# 15_EXP_IO.net
KiCad netlist of a schematic drawn in Altium Designer
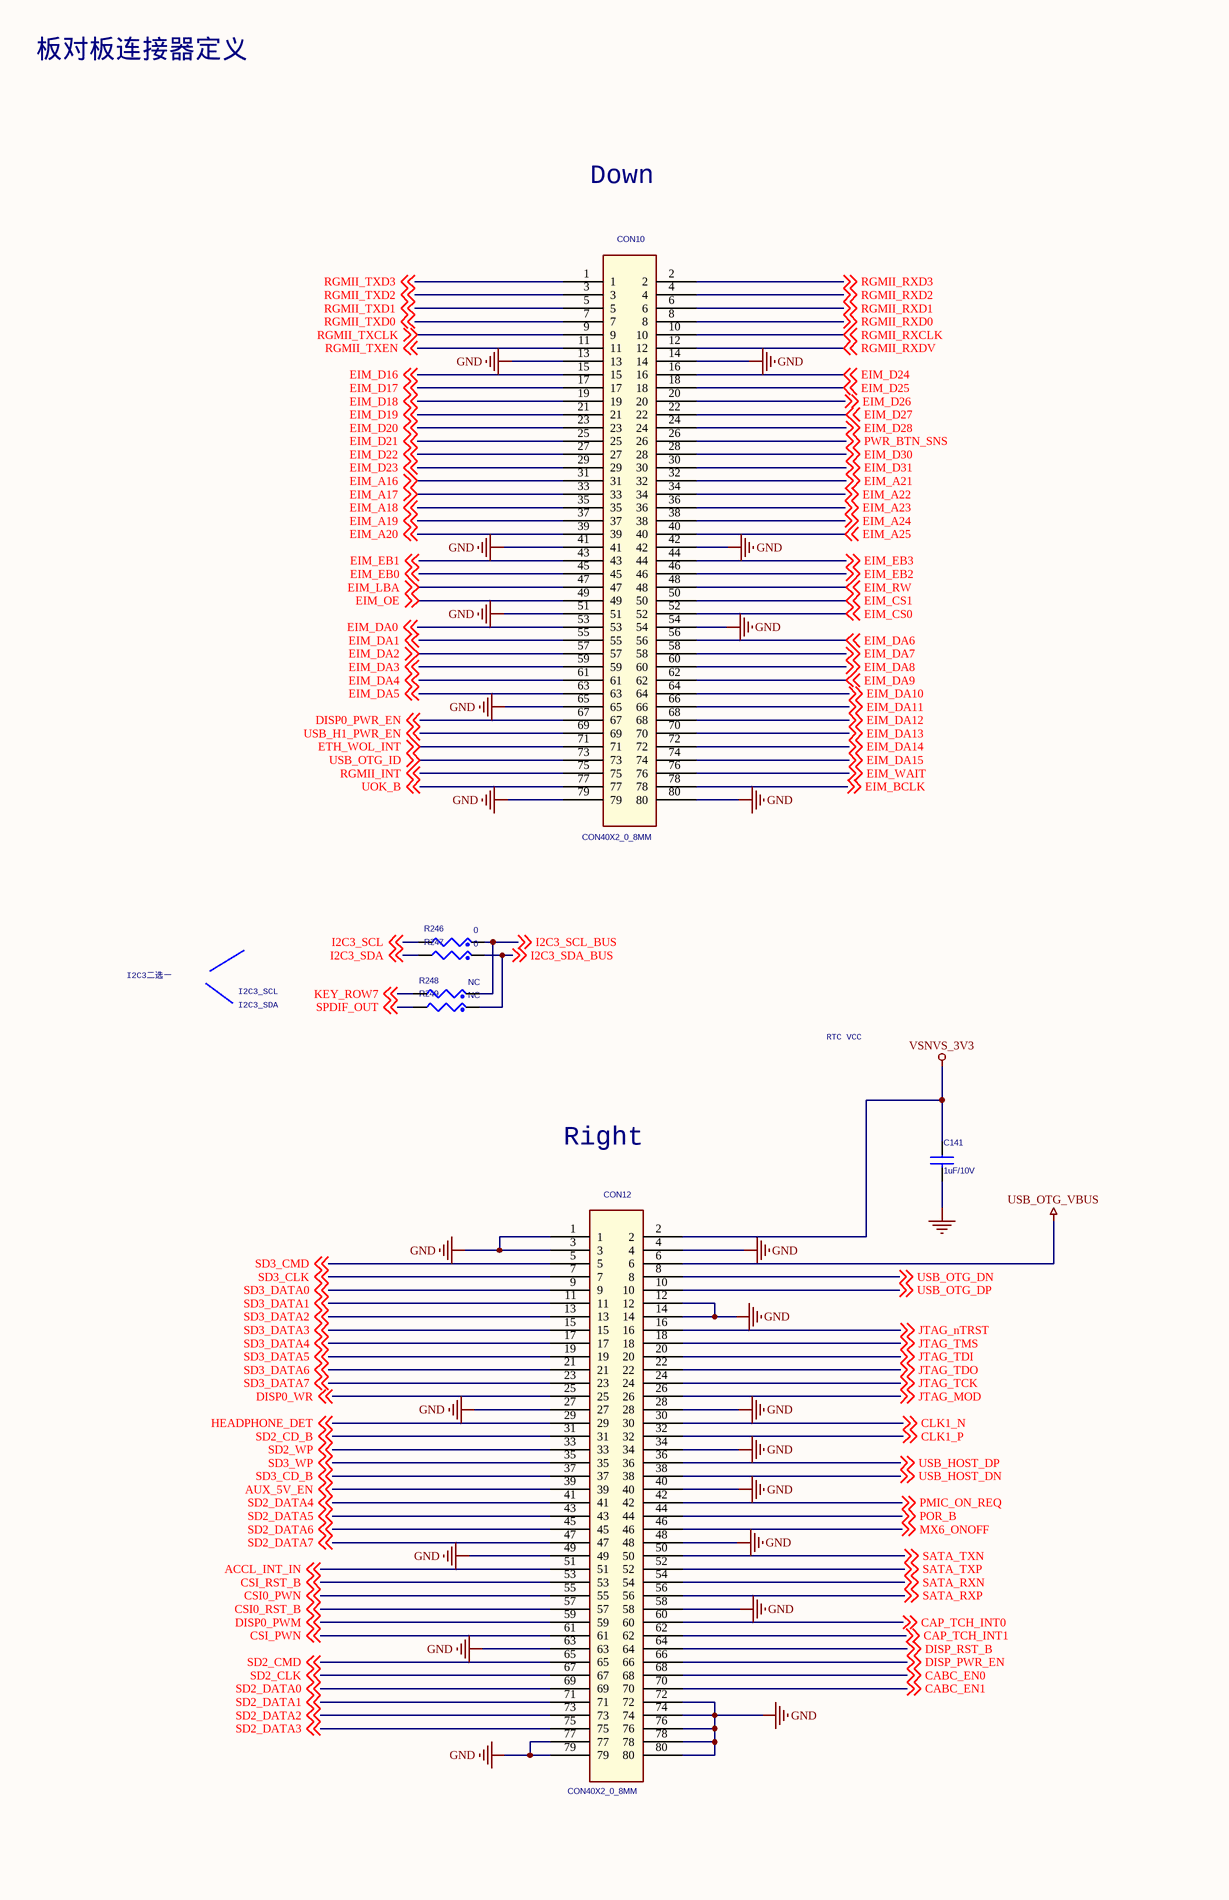
[diagram p0: 15 EXP_IO.SchDoc, left]
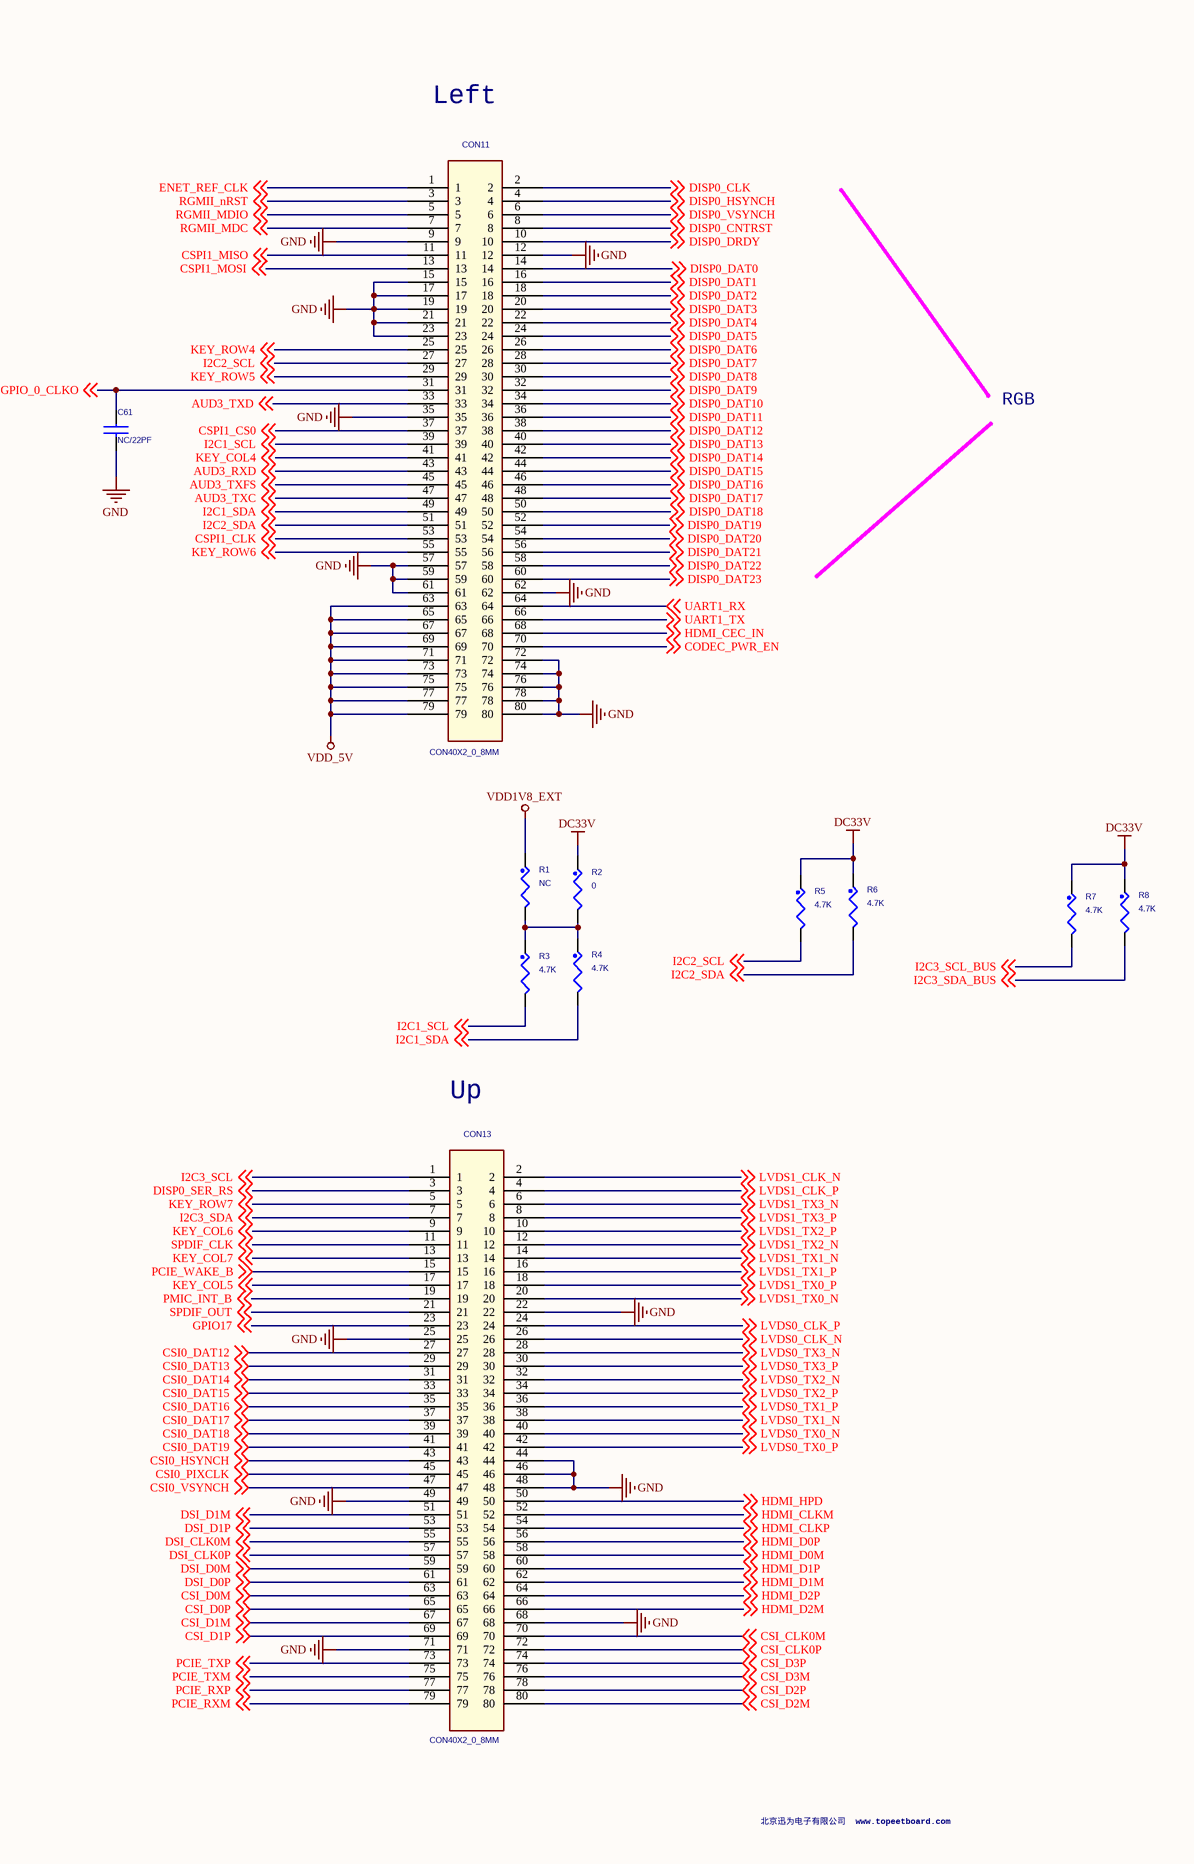
[diagram p1: 15 EXP_IO.SchDoc, right]

(export (version "E")
  (design (tool "Eeschema 10.0.6"))
  (components
    (comp (ref "C61") (value "NC/22PF") (footprint "C0603") (libsource (lib "*") (part "C0603_0_Dup1")))
    (comp (ref "C141") (value "1uF/10V") (footprint "C0603") (libsource (lib "*") (part "C0603_0_Dup1")))
    (comp (ref "CON10")
      (value "CON40X2_0_8MM")
      (footprint "CON40X2_0_8MM")
      (libsource (lib "*") (part "CON40X2_0_8MM"))
    )
    (comp (ref "CON11")
      (value "CON40X2_0_8MM")
      (footprint "CON40X2_0_8MM")
      (libsource (lib "*") (part "CON40X2_0_8MM"))
    )
    (comp (ref "CON12")
      (value "CON40X2_0_8MM")
      (footprint "CON40X2_0_8MM")
      (libsource (lib "*") (part "CON40X2_0_8MM"))
    )
    (comp (ref "CON13")
      (value "CON40X2_0_8MM")
      (footprint "CON40X2_0_8MM")
      (libsource (lib "*") (part "CON40X2_0_8MM"))
    )
    (comp (ref "R1")
      (value "NC")
      (description "RES MF ZERO OHM 1/10W -- 0402")
      (libsource (lib "*") (part "RES_Dup1"))
    )
    (comp (ref "R2")
      (value "0")
      (description "RES MF ZERO OHM 1/10W -- 0402")
      (libsource (lib "*") (part "RES_Dup1"))
    )
    (comp (ref "R3")
      (value "4.7K")
      (description "RES MF ZERO OHM 1/10W -- 0402")
      (libsource (lib "*") (part "RES_Dup1"))
    )
    (comp (ref "R4")
      (value "4.7K")
      (description "RES MF ZERO OHM 1/10W -- 0402")
      (libsource (lib "*") (part "RES_Dup1"))
    )
    (comp (ref "R5")
      (value "4.7K")
      (description "RES MF ZERO OHM 1/10W -- 0402")
      (libsource (lib "*") (part "RES_Dup1"))
    )
    (comp (ref "R6")
      (value "4.7K")
      (description "RES MF ZERO OHM 1/10W -- 0402")
      (libsource (lib "*") (part "RES_Dup1"))
    )
    (comp (ref "R7")
      (value "4.7K")
      (description "RES MF ZERO OHM 1/10W -- 0402")
      (libsource (lib "*") (part "RES_Dup1"))
    )
    (comp (ref "R8")
      (value "4.7K")
      (description "RES MF ZERO OHM 1/10W -- 0402")
      (libsource (lib "*") (part "RES_Dup1"))
    )
    (comp (ref "R246")
      (value "0")
      (description "RES MF 33 OHM 1/16W 5% 0402")
      (fields (field (name "TOLERANCE") "5%"))
      (libsource (lib "*") (part "RES_Dup1"))
    )
    (comp (ref "R247")
      (value "0")
      (description "RES MF 33 OHM 1/16W 5% 0402")
      (fields (field (name "TOLERANCE") "5%"))
      (libsource (lib "*") (part "RES_Dup1"))
    )
    (comp (ref "R248")
      (value "NC")
      (description "RES MF 33 OHM 1/16W 5% 0402")
      (fields (field (name "TOLERANCE") "5%"))
      (libsource (lib "*") (part "RES_Dup1"))
    )
    (comp (ref "R249")
      (value "NC")
      (description "RES MF 33 OHM 1/16W 5% 0402")
      (fields (field (name "TOLERANCE") "5%"))
      (libsource (lib "*") (part "RES_Dup1"))
    )
  )
  (nets
    (net (code "1") (name "ACCL_INT_IN") (class "Default")
      (node (ref "CON12") (pin "51") (pinfunction "51_51") (pintype "passive"))
    )
    (net (code "2") (name "AUD3_RXD") (class "Default")
      (node (ref "CON11") (pin "43") (pinfunction "43_43") (pintype "passive"))
    )
    (net (code "3") (name "AUD3_TXC") (class "Default")
      (node (ref "CON11") (pin "47") (pinfunction "47_47") (pintype "passive"))
    )
    (net (code "4") (name "AUD3_TXD") (class "Default")
      (node (ref "CON11") (pin "33") (pinfunction "33_33") (pintype "passive"))
    )
    (net (code "5") (name "AUD3_TXFS") (class "Default")
      (node (ref "CON11") (pin "45") (pinfunction "45_45") (pintype "passive"))
    )
    (net (code "6") (name "AUX_5V_EN") (class "Default")
      (node (ref "CON12") (pin "39") (pinfunction "39_39") (pintype "passive"))
    )
    (net (code "7") (name "CABC_EN0") (class "Default")
      (node (ref "CON12") (pin "68") (pinfunction "68_68") (pintype "passive"))
    )
    (net (code "8") (name "CABC_EN1") (class "Default")
      (node (ref "CON12") (pin "70") (pinfunction "70_70") (pintype "passive"))
    )
    (net (code "9") (name "CAP_TCH_INT0") (class "Default")
      (node (ref "CON12") (pin "60") (pinfunction "60_60") (pintype "passive"))
    )
    (net (code "10") (name "CAP_TCH_INT1") (class "Default")
      (node (ref "CON12") (pin "62") (pinfunction "62_62") (pintype "passive"))
    )
    (net (code "11") (name "CLK1_N") (class "Default")
      (node (ref "CON12") (pin "30") (pinfunction "30_30") (pintype "passive"))
    )
    (net (code "12") (name "CLK1_P") (class "Default")
      (node (ref "CON12") (pin "32") (pinfunction "32_32") (pintype "passive"))
    )
    (net (code "13") (name "CODEC_PWR_EN") (class "Default")
      (node (ref "CON11") (pin "70") (pinfunction "70_70") (pintype "passive"))
    )
    (net (code "14") (name "CSI0_DAT12") (class "Default")
      (node (ref "CON13") (pin "27") (pinfunction "27_27") (pintype "passive"))
    )
    (net (code "15") (name "CSI0_DAT13") (class "Default")
      (node (ref "CON13") (pin "29") (pinfunction "29_29") (pintype "passive"))
    )
    (net (code "16") (name "CSI0_DAT14") (class "Default")
      (node (ref "CON13") (pin "31") (pinfunction "31_31") (pintype "passive"))
    )
    (net (code "17") (name "CSI0_DAT15") (class "Default")
      (node (ref "CON13") (pin "33") (pinfunction "33_33") (pintype "passive"))
    )
    (net (code "18") (name "CSI0_DAT16") (class "Default")
      (node (ref "CON13") (pin "35") (pinfunction "35_35") (pintype "passive"))
    )
    (net (code "19") (name "CSI0_DAT17") (class "Default")
      (node (ref "CON13") (pin "37") (pinfunction "37_37") (pintype "passive"))
    )
    (net (code "20") (name "CSI0_DAT18") (class "Default")
      (node (ref "CON13") (pin "39") (pinfunction "39_39") (pintype "passive"))
    )
    (net (code "21") (name "CSI0_DAT19") (class "Default")
      (node (ref "CON13") (pin "41") (pinfunction "41_41") (pintype "passive"))
    )
    (net (code "22") (name "CSI0_HSYNCH") (class "Default")
      (node (ref "CON13") (pin "43") (pinfunction "43_43") (pintype "passive"))
    )
    (net (code "23") (name "CSI0_PIXCLK") (class "Default")
      (node (ref "CON13") (pin "45") (pinfunction "45_45") (pintype "passive"))
    )
    (net (code "24") (name "CSI0_PWN") (class "Default")
      (node (ref "CON12") (pin "55") (pinfunction "55_55") (pintype "passive"))
    )
    (net (code "25") (name "CSI0_RST_B") (class "Default")
      (node (ref "CON12") (pin "57") (pinfunction "57_57") (pintype "passive"))
    )
    (net (code "26") (name "CSI0_VSYNCH") (class "Default")
      (node (ref "CON13") (pin "47") (pinfunction "47_47") (pintype "passive"))
    )
    (net (code "27") (name "CSI_CLK0M") (class "Default")
      (node (ref "CON13") (pin "70") (pinfunction "70_70") (pintype "passive"))
    )
    (net (code "28") (name "CSI_CLK0P") (class "Default")
      (node (ref "CON13") (pin "72") (pinfunction "72_72") (pintype "passive"))
    )
    (net (code "29") (name "CSI_D0M") (class "Default")
      (node (ref "CON13") (pin "63") (pinfunction "63_63") (pintype "passive"))
    )
    (net (code "30") (name "CSI_D0P") (class "Default")
      (node (ref "CON13") (pin "65") (pinfunction "65_65") (pintype "passive"))
    )
    (net (code "31") (name "CSI_D1M") (class "Default")
      (node (ref "CON13") (pin "67") (pinfunction "67_67") (pintype "passive"))
    )
    (net (code "32") (name "CSI_D1P") (class "Default")
      (node (ref "CON13") (pin "69") (pinfunction "69_69") (pintype "passive"))
    )
    (net (code "33") (name "CSI_D2M") (class "Default")
      (node (ref "CON13") (pin "80") (pinfunction "80_80") (pintype "passive"))
    )
    (net (code "34") (name "CSI_D2P") (class "Default")
      (node (ref "CON13") (pin "78") (pinfunction "78_78") (pintype "passive"))
    )
    (net (code "35") (name "CSI_D3M") (class "Default")
      (node (ref "CON13") (pin "76") (pinfunction "76_76") (pintype "passive"))
    )
    (net (code "36") (name "CSI_D3P") (class "Default")
      (node (ref "CON13") (pin "74") (pinfunction "74_74") (pintype "passive"))
    )
    (net (code "37") (name "CSI_PWN") (class "Default")
      (node (ref "CON12") (pin "61") (pinfunction "61_61") (pintype "passive"))
    )
    (net (code "38") (name "CSI_RST_B") (class "Default")
      (node (ref "CON12") (pin "53") (pinfunction "53_53") (pintype "passive"))
    )
    (net (code "39") (name "CSPI1_CLK") (class "Default")
      (node (ref "CON11") (pin "53") (pinfunction "53_53") (pintype "passive"))
    )
    (net (code "40") (name "CSPI1_CS0") (class "Default")
      (node (ref "CON11") (pin "37") (pinfunction "37_37") (pintype "passive"))
    )
    (net (code "41") (name "CSPI1_MISO") (class "Default")
      (node (ref "CON11") (pin "11") (pinfunction "11_11") (pintype "passive"))
    )
    (net (code "42") (name "CSPI1_MOSI") (class "Default")
      (node (ref "CON11") (pin "13") (pinfunction "13_13") (pintype "passive"))
    )
    (net (code "43") (name "DC33V") (class "Default")
      (node (ref "R2") (pin "1") (pinfunction "1_1") (pintype "passive"))
      (node (ref "R5") (pin "1") (pinfunction "1_1") (pintype "passive"))
      (node (ref "R6") (pin "1") (pinfunction "1_1") (pintype "passive"))
      (node (ref "R7") (pin "1") (pinfunction "1_1") (pintype "passive"))
      (node (ref "R8") (pin "1") (pinfunction "1_1") (pintype "passive"))
    )
    (net (code "44") (name "DISP0_CLK") (class "Default")
      (node (ref "CON11") (pin "2") (pinfunction "2_2") (pintype "passive"))
    )
    (net (code "45") (name "DISP0_CNTRST") (class "Default")
      (node (ref "CON11") (pin "8") (pinfunction "8_8") (pintype "passive"))
    )
    (net (code "46") (name "DISP0_DAT0") (class "Default")
      (node (ref "CON11") (pin "14") (pinfunction "14_14") (pintype "passive"))
    )
    (net (code "47") (name "DISP0_DAT1") (class "Default")
      (node (ref "CON11") (pin "16") (pinfunction "16_16") (pintype "passive"))
    )
    (net (code "48") (name "DISP0_DAT2") (class "Default")
      (node (ref "CON11") (pin "18") (pinfunction "18_18") (pintype "passive"))
    )
    (net (code "49") (name "DISP0_DAT3") (class "Default")
      (node (ref "CON11") (pin "20") (pinfunction "20_20") (pintype "passive"))
    )
    (net (code "50") (name "DISP0_DAT4") (class "Default")
      (node (ref "CON11") (pin "22") (pinfunction "22_22") (pintype "passive"))
    )
    (net (code "51") (name "DISP0_DAT5") (class "Default")
      (node (ref "CON11") (pin "24") (pinfunction "24_24") (pintype "passive"))
    )
    (net (code "52") (name "DISP0_DAT6") (class "Default")
      (node (ref "CON11") (pin "26") (pinfunction "26_26") (pintype "passive"))
    )
    (net (code "53") (name "DISP0_DAT7") (class "Default")
      (node (ref "CON11") (pin "28") (pinfunction "28_28") (pintype "passive"))
    )
    (net (code "54") (name "DISP0_DAT8") (class "Default")
      (node (ref "CON11") (pin "30") (pinfunction "30_30") (pintype "passive"))
    )
    (net (code "55") (name "DISP0_DAT9") (class "Default")
      (node (ref "CON11") (pin "32") (pinfunction "32_32") (pintype "passive"))
    )
    (net (code "56") (name "DISP0_DAT10") (class "Default")
      (node (ref "CON11") (pin "34") (pinfunction "34_34") (pintype "passive"))
    )
    (net (code "57") (name "DISP0_DAT11") (class "Default")
      (node (ref "CON11") (pin "36") (pinfunction "36_36") (pintype "passive"))
    )
    (net (code "58") (name "DISP0_DAT12") (class "Default")
      (node (ref "CON11") (pin "38") (pinfunction "38_38") (pintype "passive"))
    )
    (net (code "59") (name "DISP0_DAT13") (class "Default")
      (node (ref "CON11") (pin "40") (pinfunction "40_40") (pintype "passive"))
    )
    (net (code "60") (name "DISP0_DAT14") (class "Default")
      (node (ref "CON11") (pin "42") (pinfunction "42_42") (pintype "passive"))
    )
    (net (code "61") (name "DISP0_DAT15") (class "Default")
      (node (ref "CON11") (pin "44") (pinfunction "44_44") (pintype "passive"))
    )
    (net (code "62") (name "DISP0_DAT16") (class "Default")
      (node (ref "CON11") (pin "46") (pinfunction "46_46") (pintype "passive"))
    )
    (net (code "63") (name "DISP0_DAT17") (class "Default")
      (node (ref "CON11") (pin "48") (pinfunction "48_48") (pintype "passive"))
    )
    (net (code "64") (name "DISP0_DAT18") (class "Default")
      (node (ref "CON11") (pin "50") (pinfunction "50_50") (pintype "passive"))
    )
    (net (code "65") (name "DISP0_DAT19") (class "Default")
      (node (ref "CON11") (pin "52") (pinfunction "52_52") (pintype "passive"))
    )
    (net (code "66") (name "DISP0_DAT20") (class "Default")
      (node (ref "CON11") (pin "54") (pinfunction "54_54") (pintype "passive"))
    )
    (net (code "67") (name "DISP0_DAT21") (class "Default")
      (node (ref "CON11") (pin "56") (pinfunction "56_56") (pintype "passive"))
    )
    (net (code "68") (name "DISP0_DAT22") (class "Default")
      (node (ref "CON11") (pin "58") (pinfunction "58_58") (pintype "passive"))
    )
    (net (code "69") (name "DISP0_DAT23") (class "Default")
      (node (ref "CON11") (pin "60") (pinfunction "60_60") (pintype "passive"))
    )
    (net (code "70") (name "DISP0_DRDY") (class "Default")
      (node (ref "CON11") (pin "10") (pinfunction "10_10") (pintype "passive"))
    )
    (net (code "71") (name "DISP0_HSYNCH") (class "Default")
      (node (ref "CON11") (pin "4") (pinfunction "4_4") (pintype "passive"))
    )
    (net (code "72") (name "DISP0_PWM") (class "Default")
      (node (ref "CON12") (pin "59") (pinfunction "59_59") (pintype "passive"))
    )
    (net (code "73") (name "DISP0_PWR_EN") (class "Default")
      (node (ref "CON10") (pin "67") (pinfunction "67_67") (pintype "passive"))
    )
    (net (code "74") (name "DISP0_SER_RS") (class "Default")
      (node (ref "CON13") (pin "3") (pinfunction "3_3") (pintype "passive"))
    )
    (net (code "75") (name "DISP0_VSYNCH") (class "Default")
      (node (ref "CON11") (pin "6") (pinfunction "6_6") (pintype "passive"))
    )
    (net (code "76") (name "DISP0_WR") (class "Default")
      (node (ref "CON12") (pin "25") (pinfunction "25_25") (pintype "passive"))
    )
    (net (code "77") (name "DISP_PWR_EN") (class "Default")
      (node (ref "CON12") (pin "66") (pinfunction "66_66") (pintype "passive"))
    )
    (net (code "78") (name "DISP_RST_B") (class "Default")
      (node (ref "CON12") (pin "64") (pinfunction "64_64") (pintype "passive"))
    )
    (net (code "79") (name "DSI_CLK0M") (class "Default")
      (node (ref "CON13") (pin "55") (pinfunction "55_55") (pintype "passive"))
    )
    (net (code "80") (name "DSI_CLK0P") (class "Default")
      (node (ref "CON13") (pin "57") (pinfunction "57_57") (pintype "passive"))
    )
    (net (code "81") (name "DSI_D0M") (class "Default")
      (node (ref "CON13") (pin "59") (pinfunction "59_59") (pintype "passive"))
    )
    (net (code "82") (name "DSI_D0P") (class "Default")
      (node (ref "CON13") (pin "61") (pinfunction "61_61") (pintype "passive"))
    )
    (net (code "83") (name "DSI_D1M") (class "Default")
      (node (ref "CON13") (pin "51") (pinfunction "51_51") (pintype "passive"))
    )
    (net (code "84") (name "DSI_D1P") (class "Default")
      (node (ref "CON13") (pin "53") (pinfunction "53_53") (pintype "passive"))
    )
    (net (code "85") (name "EIM_A16") (class "Default")
      (node (ref "CON10") (pin "31") (pinfunction "31_31") (pintype "passive"))
    )
    (net (code "86") (name "EIM_A17") (class "Default")
      (node (ref "CON10") (pin "33") (pinfunction "33_33") (pintype "passive"))
    )
    (net (code "87") (name "EIM_A18") (class "Default")
      (node (ref "CON10") (pin "35") (pinfunction "35_35") (pintype "passive"))
    )
    (net (code "88") (name "EIM_A19") (class "Default")
      (node (ref "CON10") (pin "37") (pinfunction "37_37") (pintype "passive"))
    )
    (net (code "89") (name "EIM_A20") (class "Default")
      (node (ref "CON10") (pin "39") (pinfunction "39_39") (pintype "passive"))
    )
    (net (code "90") (name "EIM_A21") (class "Default")
      (node (ref "CON10") (pin "32") (pinfunction "32_32") (pintype "passive"))
    )
    (net (code "91") (name "EIM_A22") (class "Default")
      (node (ref "CON10") (pin "34") (pinfunction "34_34") (pintype "passive"))
    )
    (net (code "92") (name "EIM_A23") (class "Default")
      (node (ref "CON10") (pin "36") (pinfunction "36_36") (pintype "passive"))
    )
    (net (code "93") (name "EIM_A24") (class "Default")
      (node (ref "CON10") (pin "38") (pinfunction "38_38") (pintype "passive"))
    )
    (net (code "94") (name "EIM_A25") (class "Default")
      (node (ref "CON10") (pin "40") (pinfunction "40_40") (pintype "passive"))
    )
    (net (code "95") (name "EIM_BCLK") (class "Default")
      (node (ref "CON10") (pin "78") (pinfunction "78_78") (pintype "passive"))
    )
    (net (code "96") (name "EIM_CS0") (class "Default")
      (node (ref "CON10") (pin "52") (pinfunction "52_52") (pintype "passive"))
    )
    (net (code "97") (name "EIM_CS1") (class "Default")
      (node (ref "CON10") (pin "50") (pinfunction "50_50") (pintype "passive"))
    )
    (net (code "98") (name "EIM_D16") (class "Default")
      (node (ref "CON10") (pin "15") (pinfunction "15_15") (pintype "passive"))
    )
    (net (code "99") (name "EIM_D17") (class "Default")
      (node (ref "CON10") (pin "17") (pinfunction "17_17") (pintype "passive"))
    )
    (net (code "100") (name "EIM_D18") (class "Default")
      (node (ref "CON10") (pin "19") (pinfunction "19_19") (pintype "passive"))
    )
    (net (code "101") (name "EIM_D19") (class "Default")
      (node (ref "CON10") (pin "21") (pinfunction "21_21") (pintype "passive"))
    )
    (net (code "102") (name "EIM_D20") (class "Default")
      (node (ref "CON10") (pin "23") (pinfunction "23_23") (pintype "passive"))
    )
    (net (code "103") (name "EIM_D21") (class "Default")
      (node (ref "CON10") (pin "25") (pinfunction "25_25") (pintype "passive"))
    )
    (net (code "104") (name "EIM_D22") (class "Default")
      (node (ref "CON10") (pin "27") (pinfunction "27_27") (pintype "passive"))
    )
    (net (code "105") (name "EIM_D23") (class "Default")
      (node (ref "CON10") (pin "29") (pinfunction "29_29") (pintype "passive"))
    )
    (net (code "106") (name "EIM_D24") (class "Default")
      (node (ref "CON10") (pin "16") (pinfunction "16_16") (pintype "passive"))
    )
    (net (code "107") (name "EIM_D25") (class "Default")
      (node (ref "CON10") (pin "18") (pinfunction "18_18") (pintype "passive"))
    )
    (net (code "108") (name "EIM_D26") (class "Default")
      (node (ref "CON10") (pin "20") (pinfunction "20_20") (pintype "passive"))
    )
    (net (code "109") (name "EIM_D27") (class "Default")
      (node (ref "CON10") (pin "22") (pinfunction "22_22") (pintype "passive"))
    )
    (net (code "110") (name "EIM_D28") (class "Default")
      (node (ref "CON10") (pin "24") (pinfunction "24_24") (pintype "passive"))
    )
    (net (code "111") (name "EIM_D30") (class "Default")
      (node (ref "CON10") (pin "28") (pinfunction "28_28") (pintype "passive"))
    )
    (net (code "112") (name "EIM_D31") (class "Default")
      (node (ref "CON10") (pin "30") (pinfunction "30_30") (pintype "passive"))
    )
    (net (code "113") (name "EIM_DA0") (class "Default")
      (node (ref "CON10") (pin "53") (pinfunction "53_53") (pintype "passive"))
    )
    (net (code "114") (name "EIM_DA1") (class "Default")
      (node (ref "CON10") (pin "55") (pinfunction "55_55") (pintype "passive"))
    )
    (net (code "115") (name "EIM_DA2") (class "Default")
      (node (ref "CON10") (pin "57") (pinfunction "57_57") (pintype "passive"))
    )
    (net (code "116") (name "EIM_DA3") (class "Default")
      (node (ref "CON10") (pin "59") (pinfunction "59_59") (pintype "passive"))
    )
    (net (code "117") (name "EIM_DA4") (class "Default")
      (node (ref "CON10") (pin "61") (pinfunction "61_61") (pintype "passive"))
    )
    (net (code "118") (name "EIM_DA5") (class "Default")
      (node (ref "CON10") (pin "63") (pinfunction "63_63") (pintype "passive"))
    )
    (net (code "119") (name "EIM_DA6") (class "Default")
      (node (ref "CON10") (pin "56") (pinfunction "56_56") (pintype "passive"))
    )
    (net (code "120") (name "EIM_DA7") (class "Default")
      (node (ref "CON10") (pin "58") (pinfunction "58_58") (pintype "passive"))
    )
    (net (code "121") (name "EIM_DA8") (class "Default")
      (node (ref "CON10") (pin "60") (pinfunction "60_60") (pintype "passive"))
    )
    (net (code "122") (name "EIM_DA9") (class "Default")
      (node (ref "CON10") (pin "62") (pinfunction "62_62") (pintype "passive"))
    )
    (net (code "123") (name "EIM_DA10") (class "Default")
      (node (ref "CON10") (pin "64") (pinfunction "64_64") (pintype "passive"))
    )
    (net (code "124") (name "EIM_DA11") (class "Default")
      (node (ref "CON10") (pin "66") (pinfunction "66_66") (pintype "passive"))
    )
    (net (code "125") (name "EIM_DA12") (class "Default")
      (node (ref "CON10") (pin "68") (pinfunction "68_68") (pintype "passive"))
    )
    (net (code "126") (name "EIM_DA13") (class "Default")
      (node (ref "CON10") (pin "70") (pinfunction "70_70") (pintype "passive"))
    )
    (net (code "127") (name "EIM_DA14") (class "Default")
      (node (ref "CON10") (pin "72") (pinfunction "72_72") (pintype "passive"))
    )
    (net (code "128") (name "EIM_DA15") (class "Default")
      (node (ref "CON10") (pin "74") (pinfunction "74_74") (pintype "passive"))
    )
    (net (code "129") (name "EIM_EB0") (class "Default")
      (node (ref "CON10") (pin "45") (pinfunction "45_45") (pintype "passive"))
    )
    (net (code "130") (name "EIM_EB1") (class "Default")
      (node (ref "CON10") (pin "43") (pinfunction "43_43") (pintype "passive"))
    )
    (net (code "131") (name "EIM_EB2") (class "Default")
      (node (ref "CON10") (pin "46") (pinfunction "46_46") (pintype "passive"))
    )
    (net (code "132") (name "EIM_EB3") (class "Default")
      (node (ref "CON10") (pin "44") (pinfunction "44_44") (pintype "passive"))
    )
    (net (code "133") (name "EIM_LBA") (class "Default")
      (node (ref "CON10") (pin "47") (pinfunction "47_47") (pintype "passive"))
    )
    (net (code "134") (name "EIM_OE") (class "Default")
      (node (ref "CON10") (pin "49") (pinfunction "49_49") (pintype "passive"))
    )
    (net (code "135") (name "EIM_RW") (class "Default")
      (node (ref "CON10") (pin "48") (pinfunction "48_48") (pintype "passive"))
    )
    (net (code "136") (name "EIM_WAIT") (class "Default")
      (node (ref "CON10") (pin "76") (pinfunction "76_76") (pintype "passive"))
    )
    (net (code "137") (name "ENET_REF_CLK") (class "Default")
      (node (ref "CON11") (pin "1") (pinfunction "1_1") (pintype "passive"))
    )
    (net (code "138") (name "ETH_WOL_INT") (class "Default")
      (node (ref "CON10") (pin "71") (pinfunction "71_71") (pintype "passive"))
    )
    (net (code "139") (name "GND") (class "Default")
      (node (ref "C141") (pin "2") (pinfunction "2_2") (pintype "passive"))
      (node (ref "C61") (pin "2") (pinfunction "2_2") (pintype "passive"))
      (node (ref "CON10") (pin "13") (pinfunction "13_13") (pintype "passive"))
      (node (ref "CON10") (pin "14") (pinfunction "14_14") (pintype "passive"))
      (node (ref "CON10") (pin "41") (pinfunction "41_41") (pintype "passive"))
      (node (ref "CON10") (pin "42") (pinfunction "42_42") (pintype "passive"))
      (node (ref "CON10") (pin "51") (pinfunction "51_51") (pintype "passive"))
      (node (ref "CON10") (pin "54") (pinfunction "54_54") (pintype "passive"))
      (node (ref "CON10") (pin "65") (pinfunction "65_65") (pintype "passive"))
      (node (ref "CON10") (pin "79") (pinfunction "79_79") (pintype "passive"))
      (node (ref "CON10") (pin "80") (pinfunction "80_80") (pintype "passive"))
      (node (ref "CON11") (pin "12") (pinfunction "12_12") (pintype "passive"))
      (node (ref "CON11") (pin "15") (pinfunction "15_15") (pintype "passive"))
      (node (ref "CON11") (pin "17") (pinfunction "17_17") (pintype "passive"))
      (node (ref "CON11") (pin "19") (pinfunction "19_19") (pintype "passive"))
      (node (ref "CON11") (pin "21") (pinfunction "21_21") (pintype "passive"))
      (node (ref "CON11") (pin "23") (pinfunction "23_23") (pintype "passive"))
      (node (ref "CON11") (pin "35") (pinfunction "35_35") (pintype "passive"))
      (node (ref "CON11") (pin "57") (pinfunction "57_57") (pintype "passive"))
      (node (ref "CON11") (pin "59") (pinfunction "59_59") (pintype "passive"))
      (node (ref "CON11") (pin "61") (pinfunction "61_61") (pintype "passive"))
      (node (ref "CON11") (pin "62") (pinfunction "62_62") (pintype "passive"))
      (node (ref "CON11") (pin "72") (pinfunction "72_72") (pintype "passive"))
      (node (ref "CON11") (pin "74") (pinfunction "74_74") (pintype "passive"))
      (node (ref "CON11") (pin "76") (pinfunction "76_76") (pintype "passive"))
      (node (ref "CON11") (pin "78") (pinfunction "78_78") (pintype "passive"))
      (node (ref "CON11") (pin "80") (pinfunction "80_80") (pintype "passive"))
      (node (ref "CON11") (pin "9") (pinfunction "9_9") (pintype "passive"))
      (node (ref "CON12") (pin "1") (pinfunction "1_1") (pintype "passive"))
      (node (ref "CON12") (pin "12") (pinfunction "12_12") (pintype "passive"))
      (node (ref "CON12") (pin "14") (pinfunction "14_14") (pintype "passive"))
      (node (ref "CON12") (pin "27") (pinfunction "27_27") (pintype "passive"))
      (node (ref "CON12") (pin "28") (pinfunction "28_28") (pintype "passive"))
      (node (ref "CON12") (pin "3") (pinfunction "3_3") (pintype "passive"))
      (node (ref "CON12") (pin "34") (pinfunction "34_34") (pintype "passive"))
      (node (ref "CON12") (pin "4") (pinfunction "4_4") (pintype "passive"))
      (node (ref "CON12") (pin "40") (pinfunction "40_40") (pintype "passive"))
      (node (ref "CON12") (pin "48") (pinfunction "48_48") (pintype "passive"))
      (node (ref "CON12") (pin "49") (pinfunction "49_49") (pintype "passive"))
      (node (ref "CON12") (pin "58") (pinfunction "58_58") (pintype "passive"))
      (node (ref "CON12") (pin "63") (pinfunction "63_63") (pintype "passive"))
      (node (ref "CON12") (pin "72") (pinfunction "72_72") (pintype "passive"))
      (node (ref "CON12") (pin "74") (pinfunction "74_74") (pintype "passive"))
      (node (ref "CON12") (pin "76") (pinfunction "76_76") (pintype "passive"))
      (node (ref "CON12") (pin "77") (pinfunction "77_77") (pintype "passive"))
      (node (ref "CON12") (pin "78") (pinfunction "78_78") (pintype "passive"))
      (node (ref "CON12") (pin "79") (pinfunction "79_79") (pintype "passive"))
      (node (ref "CON12") (pin "80") (pinfunction "80_80") (pintype "passive"))
      (node (ref "CON13") (pin "22") (pinfunction "22_22") (pintype "passive"))
      (node (ref "CON13") (pin "25") (pinfunction "25_25") (pintype "passive"))
      (node (ref "CON13") (pin "44") (pinfunction "44_44") (pintype "passive"))
      (node (ref "CON13") (pin "46") (pinfunction "46_46") (pintype "passive"))
      (node (ref "CON13") (pin "48") (pinfunction "48_48") (pintype "passive"))
      (node (ref "CON13") (pin "49") (pinfunction "49_49") (pintype "passive"))
      (node (ref "CON13") (pin "68") (pinfunction "68_68") (pintype "passive"))
      (node (ref "CON13") (pin "71") (pinfunction "71_71") (pintype "passive"))
    )
    (net (code "140") (name "GPIO17") (class "Default")
      (node (ref "CON13") (pin "23") (pinfunction "23_23") (pintype "passive"))
    )
    (net (code "141") (name "GPIO_0_CLKO") (class "Default")
      (node (ref "C61") (pin "1") (pinfunction "1_1") (pintype "passive"))
      (node (ref "CON11") (pin "31") (pinfunction "31_31") (pintype "passive"))
    )
    (net (code "142") (name "HDMI_CEC_IN") (class "Default")
      (node (ref "CON11") (pin "68") (pinfunction "68_68") (pintype "passive"))
    )
    (net (code "143") (name "HDMI_CLKM") (class "Default")
      (node (ref "CON13") (pin "52") (pinfunction "52_52") (pintype "passive"))
    )
    (net (code "144") (name "HDMI_CLKP") (class "Default")
      (node (ref "CON13") (pin "54") (pinfunction "54_54") (pintype "passive"))
    )
    (net (code "145") (name "HDMI_D0M") (class "Default")
      (node (ref "CON13") (pin "58") (pinfunction "58_58") (pintype "passive"))
    )
    (net (code "146") (name "HDMI_D0P") (class "Default")
      (node (ref "CON13") (pin "56") (pinfunction "56_56") (pintype "passive"))
    )
    (net (code "147") (name "HDMI_D1M") (class "Default")
      (node (ref "CON13") (pin "62") (pinfunction "62_62") (pintype "passive"))
    )
    (net (code "148") (name "HDMI_D1P") (class "Default")
      (node (ref "CON13") (pin "60") (pinfunction "60_60") (pintype "passive"))
    )
    (net (code "149") (name "HDMI_D2M") (class "Default")
      (node (ref "CON13") (pin "66") (pinfunction "66_66") (pintype "passive"))
    )
    (net (code "150") (name "HDMI_D2P") (class "Default")
      (node (ref "CON13") (pin "64") (pinfunction "64_64") (pintype "passive"))
    )
    (net (code "151") (name "HDMI_HPD") (class "Default")
      (node (ref "CON13") (pin "50") (pinfunction "50_50") (pintype "passive"))
    )
    (net (code "152") (name "HEADPHONE_DET") (class "Default")
      (node (ref "CON12") (pin "29") (pinfunction "29_29") (pintype "passive"))
    )
    (net (code "153") (name "I2C1_SCL") (class "Default")
      (node (ref "CON11") (pin "39") (pinfunction "39_39") (pintype "passive"))
      (node (ref "R3") (pin "2") (pinfunction "2_2") (pintype "passive"))
    )
    (net (code "154") (name "I2C1_SDA") (class "Default")
      (node (ref "CON11") (pin "49") (pinfunction "49_49") (pintype "passive"))
      (node (ref "R4") (pin "2") (pinfunction "2_2") (pintype "passive"))
    )
    (net (code "155") (name "I2C2_SCL") (class "Default")
      (node (ref "CON11") (pin "27") (pinfunction "27_27") (pintype "passive"))
      (node (ref "R5") (pin "2") (pinfunction "2_2") (pintype "passive"))
    )
    (net (code "156") (name "I2C2_SDA") (class "Default")
      (node (ref "CON11") (pin "51") (pinfunction "51_51") (pintype "passive"))
      (node (ref "R6") (pin "2") (pinfunction "2_2") (pintype "passive"))
    )
    (net (code "157") (name "I2C3_SCL") (class "Default")
      (node (ref "CON13") (pin "1") (pinfunction "1_1") (pintype "passive"))
      (node (ref "R246") (pin "2") (pinfunction "2_2") (pintype "passive"))
    )
    (net (code "158") (name "I2C3_SCL_BUS") (class "Default")
      (node (ref "R246") (pin "1") (pinfunction "1_1") (pintype "passive"))
      (node (ref "R248") (pin "1") (pinfunction "1_1") (pintype "passive"))
      (node (ref "R7") (pin "2") (pinfunction "2_2") (pintype "passive"))
    )
    (net (code "159") (name "I2C3_SDA") (class "Default")
      (node (ref "CON13") (pin "7") (pinfunction "7_7") (pintype "passive"))
      (node (ref "R247") (pin "2") (pinfunction "2_2") (pintype "passive"))
    )
    (net (code "160") (name "I2C3_SDA_BUS") (class "Default")
      (node (ref "R247") (pin "1") (pinfunction "1_1") (pintype "passive"))
      (node (ref "R249") (pin "1") (pinfunction "1_1") (pintype "passive"))
      (node (ref "R8") (pin "2") (pinfunction "2_2") (pintype "passive"))
    )
    (net (code "161") (name "JTAG_MOD") (class "Default")
      (node (ref "CON12") (pin "26") (pinfunction "26_26") (pintype "passive"))
    )
    (net (code "162") (name "JTAG_TCK") (class "Default")
      (node (ref "CON12") (pin "24") (pinfunction "24_24") (pintype "passive"))
    )
    (net (code "163") (name "JTAG_TDI") (class "Default")
      (node (ref "CON12") (pin "20") (pinfunction "20_20") (pintype "passive"))
    )
    (net (code "164") (name "JTAG_TDO") (class "Default")
      (node (ref "CON12") (pin "22") (pinfunction "22_22") (pintype "passive"))
    )
    (net (code "165") (name "JTAG_TMS") (class "Default")
      (node (ref "CON12") (pin "18") (pinfunction "18_18") (pintype "passive"))
    )
    (net (code "166") (name "JTAG_nTRST") (class "Default")
      (node (ref "CON12") (pin "16") (pinfunction "16_16") (pintype "passive"))
    )
    (net (code "167") (name "KEY_COL4") (class "Default")
      (node (ref "CON11") (pin "41") (pinfunction "41_41") (pintype "passive"))
    )
    (net (code "168") (name "KEY_COL5") (class "Default")
      (node (ref "CON13") (pin "17") (pinfunction "17_17") (pintype "passive"))
    )
    (net (code "169") (name "KEY_COL6") (class "Default")
      (node (ref "CON13") (pin "9") (pinfunction "9_9") (pintype "passive"))
    )
    (net (code "170") (name "KEY_COL7") (class "Default")
      (node (ref "CON13") (pin "13") (pinfunction "13_13") (pintype "passive"))
    )
    (net (code "171") (name "KEY_ROW4") (class "Default")
      (node (ref "CON11") (pin "25") (pinfunction "25_25") (pintype "passive"))
    )
    (net (code "172") (name "KEY_ROW5") (class "Default")
      (node (ref "CON11") (pin "29") (pinfunction "29_29") (pintype "passive"))
    )
    (net (code "173") (name "KEY_ROW6") (class "Default")
      (node (ref "CON11") (pin "55") (pinfunction "55_55") (pintype "passive"))
    )
    (net (code "174") (name "KEY_ROW7") (class "Default")
      (node (ref "CON13") (pin "5") (pinfunction "5_5") (pintype "passive"))
      (node (ref "R248") (pin "2") (pinfunction "2_2") (pintype "passive"))
    )
    (net (code "175") (name "LVDS0_CLK_N") (class "Default")
      (node (ref "CON13") (pin "26") (pinfunction "26_26") (pintype "passive"))
    )
    (net (code "176") (name "LVDS0_CLK_P") (class "Default")
      (node (ref "CON13") (pin "24") (pinfunction "24_24") (pintype "passive"))
    )
    (net (code "177") (name "LVDS0_TX0_N") (class "Default")
      (node (ref "CON13") (pin "40") (pinfunction "40_40") (pintype "passive"))
    )
    (net (code "178") (name "LVDS0_TX0_P") (class "Default")
      (node (ref "CON13") (pin "42") (pinfunction "42_42") (pintype "passive"))
    )
    (net (code "179") (name "LVDS0_TX1_N") (class "Default")
      (node (ref "CON13") (pin "38") (pinfunction "38_38") (pintype "passive"))
    )
    (net (code "180") (name "LVDS0_TX1_P") (class "Default")
      (node (ref "CON13") (pin "36") (pinfunction "36_36") (pintype "passive"))
    )
    (net (code "181") (name "LVDS0_TX2_N") (class "Default")
      (node (ref "CON13") (pin "32") (pinfunction "32_32") (pintype "passive"))
    )
    (net (code "182") (name "LVDS0_TX2_P") (class "Default")
      (node (ref "CON13") (pin "34") (pinfunction "34_34") (pintype "passive"))
    )
    (net (code "183") (name "LVDS0_TX3_N") (class "Default")
      (node (ref "CON13") (pin "28") (pinfunction "28_28") (pintype "passive"))
    )
    (net (code "184") (name "LVDS0_TX3_P") (class "Default")
      (node (ref "CON13") (pin "30") (pinfunction "30_30") (pintype "passive"))
    )
    (net (code "185") (name "LVDS1_CLK_N") (class "Default")
      (node (ref "CON13") (pin "2") (pinfunction "2_2") (pintype "passive"))
    )
    (net (code "186") (name "LVDS1_CLK_P") (class "Default")
      (node (ref "CON13") (pin "4") (pinfunction "4_4") (pintype "passive"))
    )
    (net (code "187") (name "LVDS1_TX0_N") (class "Default")
      (node (ref "CON13") (pin "20") (pinfunction "20_20") (pintype "passive"))
    )
    (net (code "188") (name "LVDS1_TX0_P") (class "Default")
      (node (ref "CON13") (pin "18") (pinfunction "18_18") (pintype "passive"))
    )
    (net (code "189") (name "LVDS1_TX1_N") (class "Default")
      (node (ref "CON13") (pin "14") (pinfunction "14_14") (pintype "passive"))
    )
    (net (code "190") (name "LVDS1_TX1_P") (class "Default")
      (node (ref "CON13") (pin "16") (pinfunction "16_16") (pintype "passive"))
    )
    (net (code "191") (name "LVDS1_TX2_N") (class "Default")
      (node (ref "CON13") (pin "12") (pinfunction "12_12") (pintype "passive"))
    )
    (net (code "192") (name "LVDS1_TX2_P") (class "Default")
      (node (ref "CON13") (pin "10") (pinfunction "10_10") (pintype "passive"))
    )
    (net (code "193") (name "LVDS1_TX3_N") (class "Default")
      (node (ref "CON13") (pin "6") (pinfunction "6_6") (pintype "passive"))
    )
    (net (code "194") (name "LVDS1_TX3_P") (class "Default")
      (node (ref "CON13") (pin "8") (pinfunction "8_8") (pintype "passive"))
    )
    (net (code "195") (name "MX6_ONOFF") (class "Default")
      (node (ref "CON12") (pin "46") (pinfunction "46_46") (pintype "passive"))
    )
    (net (code "196") (name "Net-(R1-Pad2)") (class "Default")
      (node (ref "R1") (pin "2") (pinfunction "2_2") (pintype "passive"))
      (node (ref "R2") (pin "2") (pinfunction "2_2") (pintype "passive"))
      (node (ref "R3") (pin "1") (pinfunction "1_1") (pintype "passive"))
      (node (ref "R4") (pin "1") (pinfunction "1_1") (pintype "passive"))
    )
    (net (code "197") (name "PCIE_RXM") (class "Default")
      (node (ref "CON13") (pin "79") (pinfunction "79_79") (pintype "passive"))
    )
    (net (code "198") (name "PCIE_RXP") (class "Default")
      (node (ref "CON13") (pin "77") (pinfunction "77_77") (pintype "passive"))
    )
    (net (code "199") (name "PCIE_TXM") (class "Default")
      (node (ref "CON13") (pin "75") (pinfunction "75_75") (pintype "passive"))
    )
    (net (code "200") (name "PCIE_TXP") (class "Default")
      (node (ref "CON13") (pin "73") (pinfunction "73_73") (pintype "passive"))
    )
    (net (code "201") (name "PCIE_WAKE_B") (class "Default")
      (node (ref "CON13") (pin "15") (pinfunction "15_15") (pintype "passive"))
    )
    (net (code "202") (name "PMIC_INT_B") (class "Default")
      (node (ref "CON13") (pin "19") (pinfunction "19_19") (pintype "passive"))
    )
    (net (code "203") (name "PMIC_ON_REQ") (class "Default")
      (node (ref "CON12") (pin "42") (pinfunction "42_42") (pintype "passive"))
    )
    (net (code "204") (name "POR_B") (class "Default")
      (node (ref "CON12") (pin "44") (pinfunction "44_44") (pintype "passive"))
    )
    (net (code "205") (name "PWR_BTN_SNS") (class "Default")
      (node (ref "CON10") (pin "26") (pinfunction "26_26") (pintype "passive"))
    )
    (net (code "206") (name "RGMII_INT") (class "Default")
      (node (ref "CON10") (pin "75") (pinfunction "75_75") (pintype "passive"))
    )
    (net (code "207") (name "RGMII_MDC") (class "Default")
      (node (ref "CON11") (pin "7") (pinfunction "7_7") (pintype "passive"))
    )
    (net (code "208") (name "RGMII_MDIO") (class "Default")
      (node (ref "CON11") (pin "5") (pinfunction "5_5") (pintype "passive"))
    )
    (net (code "209") (name "RGMII_RXCLK") (class "Default")
      (node (ref "CON10") (pin "10") (pinfunction "10_10") (pintype "passive"))
    )
    (net (code "210") (name "RGMII_RXD0") (class "Default")
      (node (ref "CON10") (pin "8") (pinfunction "8_8") (pintype "passive"))
    )
    (net (code "211") (name "RGMII_RXD1") (class "Default")
      (node (ref "CON10") (pin "6") (pinfunction "6_6") (pintype "passive"))
    )
    (net (code "212") (name "RGMII_RXD2") (class "Default")
      (node (ref "CON10") (pin "4") (pinfunction "4_4") (pintype "passive"))
    )
    (net (code "213") (name "RGMII_RXD3") (class "Default")
      (node (ref "CON10") (pin "2") (pinfunction "2_2") (pintype "passive"))
    )
    (net (code "214") (name "RGMII_RXDV") (class "Default")
      (node (ref "CON10") (pin "12") (pinfunction "12_12") (pintype "passive"))
    )
    (net (code "215") (name "RGMII_TXCLK") (class "Default")
      (node (ref "CON10") (pin "9") (pinfunction "9_9") (pintype "passive"))
    )
    (net (code "216") (name "RGMII_TXD0") (class "Default")
      (node (ref "CON10") (pin "7") (pinfunction "7_7") (pintype "passive"))
    )
    (net (code "217") (name "RGMII_TXD1") (class "Default")
      (node (ref "CON10") (pin "5") (pinfunction "5_5") (pintype "passive"))
    )
    (net (code "218") (name "RGMII_TXD2") (class "Default")
      (node (ref "CON10") (pin "3") (pinfunction "3_3") (pintype "passive"))
    )
    (net (code "219") (name "RGMII_TXD3") (class "Default")
      (node (ref "CON10") (pin "1") (pinfunction "1_1") (pintype "passive"))
    )
    (net (code "220") (name "RGMII_TXEN") (class "Default")
      (node (ref "CON10") (pin "11") (pinfunction "11_11") (pintype "passive"))
    )
    (net (code "221") (name "RGMII_nRST") (class "Default")
      (node (ref "CON11") (pin "3") (pinfunction "3_3") (pintype "passive"))
    )
    (net (code "222") (name "SATA_RXN") (class "Default")
      (node (ref "CON12") (pin "54") (pinfunction "54_54") (pintype "passive"))
    )
    (net (code "223") (name "SATA_RXP") (class "Default")
      (node (ref "CON12") (pin "56") (pinfunction "56_56") (pintype "passive"))
    )
    (net (code "224") (name "SATA_TXN") (class "Default")
      (node (ref "CON12") (pin "50") (pinfunction "50_50") (pintype "passive"))
    )
    (net (code "225") (name "SATA_TXP") (class "Default")
      (node (ref "CON12") (pin "52") (pinfunction "52_52") (pintype "passive"))
    )
    (net (code "226") (name "SD2_CD_B") (class "Default")
      (node (ref "CON12") (pin "31") (pinfunction "31_31") (pintype "passive"))
    )
    (net (code "227") (name "SD2_CLK") (class "Default")
      (node (ref "CON12") (pin "67") (pinfunction "67_67") (pintype "passive"))
    )
    (net (code "228") (name "SD2_CMD") (class "Default")
      (node (ref "CON12") (pin "65") (pinfunction "65_65") (pintype "passive"))
    )
    (net (code "229") (name "SD2_DATA0") (class "Default")
      (node (ref "CON12") (pin "69") (pinfunction "69_69") (pintype "passive"))
    )
    (net (code "230") (name "SD2_DATA1") (class "Default")
      (node (ref "CON12") (pin "71") (pinfunction "71_71") (pintype "passive"))
    )
    (net (code "231") (name "SD2_DATA2") (class "Default")
      (node (ref "CON12") (pin "73") (pinfunction "73_73") (pintype "passive"))
    )
    (net (code "232") (name "SD2_DATA3") (class "Default")
      (node (ref "CON12") (pin "75") (pinfunction "75_75") (pintype "passive"))
    )
    (net (code "233") (name "SD2_DATA4") (class "Default")
      (node (ref "CON12") (pin "41") (pinfunction "41_41") (pintype "passive"))
    )
    (net (code "234") (name "SD2_DATA5") (class "Default")
      (node (ref "CON12") (pin "43") (pinfunction "43_43") (pintype "passive"))
    )
    (net (code "235") (name "SD2_DATA6") (class "Default")
      (node (ref "CON12") (pin "45") (pinfunction "45_45") (pintype "passive"))
    )
    (net (code "236") (name "SD2_DATA7") (class "Default")
      (node (ref "CON12") (pin "47") (pinfunction "47_47") (pintype "passive"))
    )
    (net (code "237") (name "SD2_WP") (class "Default")
      (node (ref "CON12") (pin "33") (pinfunction "33_33") (pintype "passive"))
    )
    (net (code "238") (name "SD3_CD_B") (class "Default")
      (node (ref "CON12") (pin "37") (pinfunction "37_37") (pintype "passive"))
    )
    (net (code "239") (name "SD3_CLK") (class "Default")
      (node (ref "CON12") (pin "7") (pinfunction "7_7") (pintype "passive"))
    )
    (net (code "240") (name "SD3_CMD") (class "Default")
      (node (ref "CON12") (pin "5") (pinfunction "5_5") (pintype "passive"))
    )
    (net (code "241") (name "SD3_DATA0") (class "Default")
      (node (ref "CON12") (pin "9") (pinfunction "9_9") (pintype "passive"))
    )
    (net (code "242") (name "SD3_DATA1") (class "Default")
      (node (ref "CON12") (pin "11") (pinfunction "11_11") (pintype "passive"))
    )
    (net (code "243") (name "SD3_DATA2") (class "Default")
      (node (ref "CON12") (pin "13") (pinfunction "13_13") (pintype "passive"))
    )
    (net (code "244") (name "SD3_DATA3") (class "Default")
      (node (ref "CON12") (pin "15") (pinfunction "15_15") (pintype "passive"))
    )
    (net (code "245") (name "SD3_DATA4") (class "Default")
      (node (ref "CON12") (pin "17") (pinfunction "17_17") (pintype "passive"))
    )
    (net (code "246") (name "SD3_DATA5") (class "Default")
      (node (ref "CON12") (pin "19") (pinfunction "19_19") (pintype "passive"))
    )
    (net (code "247") (name "SD3_DATA6") (class "Default")
      (node (ref "CON12") (pin "21") (pinfunction "21_21") (pintype "passive"))
    )
    (net (code "248") (name "SD3_DATA7") (class "Default")
      (node (ref "CON12") (pin "23") (pinfunction "23_23") (pintype "passive"))
    )
    (net (code "249") (name "SD3_WP") (class "Default")
      (node (ref "CON12") (pin "35") (pinfunction "35_35") (pintype "passive"))
    )
    (net (code "250") (name "SPDIF_CLK") (class "Default")
      (node (ref "CON13") (pin "11") (pinfunction "11_11") (pintype "passive"))
    )
    (net (code "251") (name "SPDIF_OUT") (class "Default")
      (node (ref "CON13") (pin "21") (pinfunction "21_21") (pintype "passive"))
      (node (ref "R249") (pin "2") (pinfunction "2_2") (pintype "passive"))
    )
    (net (code "252") (name "UART1_RX") (class "Default")
      (node (ref "CON11") (pin "64") (pinfunction "64_64") (pintype "passive"))
    )
    (net (code "253") (name "UART1_TX") (class "Default")
      (node (ref "CON11") (pin "66") (pinfunction "66_66") (pintype "passive"))
    )
    (net (code "254") (name "UOK_B") (class "Default")
      (node (ref "CON10") (pin "77") (pinfunction "77_77") (pintype "passive"))
    )
    (net (code "255") (name "USB_H1_PWR_EN") (class "Default")
      (node (ref "CON10") (pin "69") (pinfunction "69_69") (pintype "passive"))
    )
    (net (code "256") (name "USB_HOST_DN") (class "Default")
      (node (ref "CON12") (pin "38") (pinfunction "38_38") (pintype "passive"))
    )
    (net (code "257") (name "USB_HOST_DP") (class "Default")
      (node (ref "CON12") (pin "36") (pinfunction "36_36") (pintype "passive"))
    )
    (net (code "258") (name "USB_OTG_DN") (class "Default")
      (node (ref "CON12") (pin "8") (pinfunction "8_8") (pintype "passive"))
    )
    (net (code "259") (name "USB_OTG_DP") (class "Default")
      (node (ref "CON12") (pin "10") (pinfunction "10_10") (pintype "passive"))
    )
    (net (code "260") (name "USB_OTG_ID") (class "Default")
      (node (ref "CON10") (pin "73") (pinfunction "73_73") (pintype "passive"))
    )
    (net (code "261") (name "USB_OTG_VBUS") (class "Default")
      (node (ref "CON12") (pin "6") (pinfunction "6_6") (pintype "passive"))
    )
    (net (code "262") (name "VDD1V8_EXT") (class "Default")
      (node (ref "R1") (pin "1") (pinfunction "1_1") (pintype "passive"))
    )
    (net (code "263") (name "VDD_5V") (class "Default")
      (node (ref "CON11") (pin "63") (pinfunction "63_63") (pintype "passive"))
      (node (ref "CON11") (pin "65") (pinfunction "65_65") (pintype "passive"))
      (node (ref "CON11") (pin "67") (pinfunction "67_67") (pintype "passive"))
      (node (ref "CON11") (pin "69") (pinfunction "69_69") (pintype "passive"))
      (node (ref "CON11") (pin "71") (pinfunction "71_71") (pintype "passive"))
      (node (ref "CON11") (pin "73") (pinfunction "73_73") (pintype "passive"))
      (node (ref "CON11") (pin "75") (pinfunction "75_75") (pintype "passive"))
      (node (ref "CON11") (pin "77") (pinfunction "77_77") (pintype "passive"))
      (node (ref "CON11") (pin "79") (pinfunction "79_79") (pintype "passive"))
    )
    (net (code "264") (name "VSNVS_3V3") (class "Default")
      (node (ref "C141") (pin "1") (pinfunction "1_1") (pintype "passive"))
      (node (ref "CON12") (pin "2") (pinfunction "2_2") (pintype "passive"))
    )
  )
)
